# 48-17V_Buck_Converter.net
KiCad netlist of a schematic drawn in Altium Designer
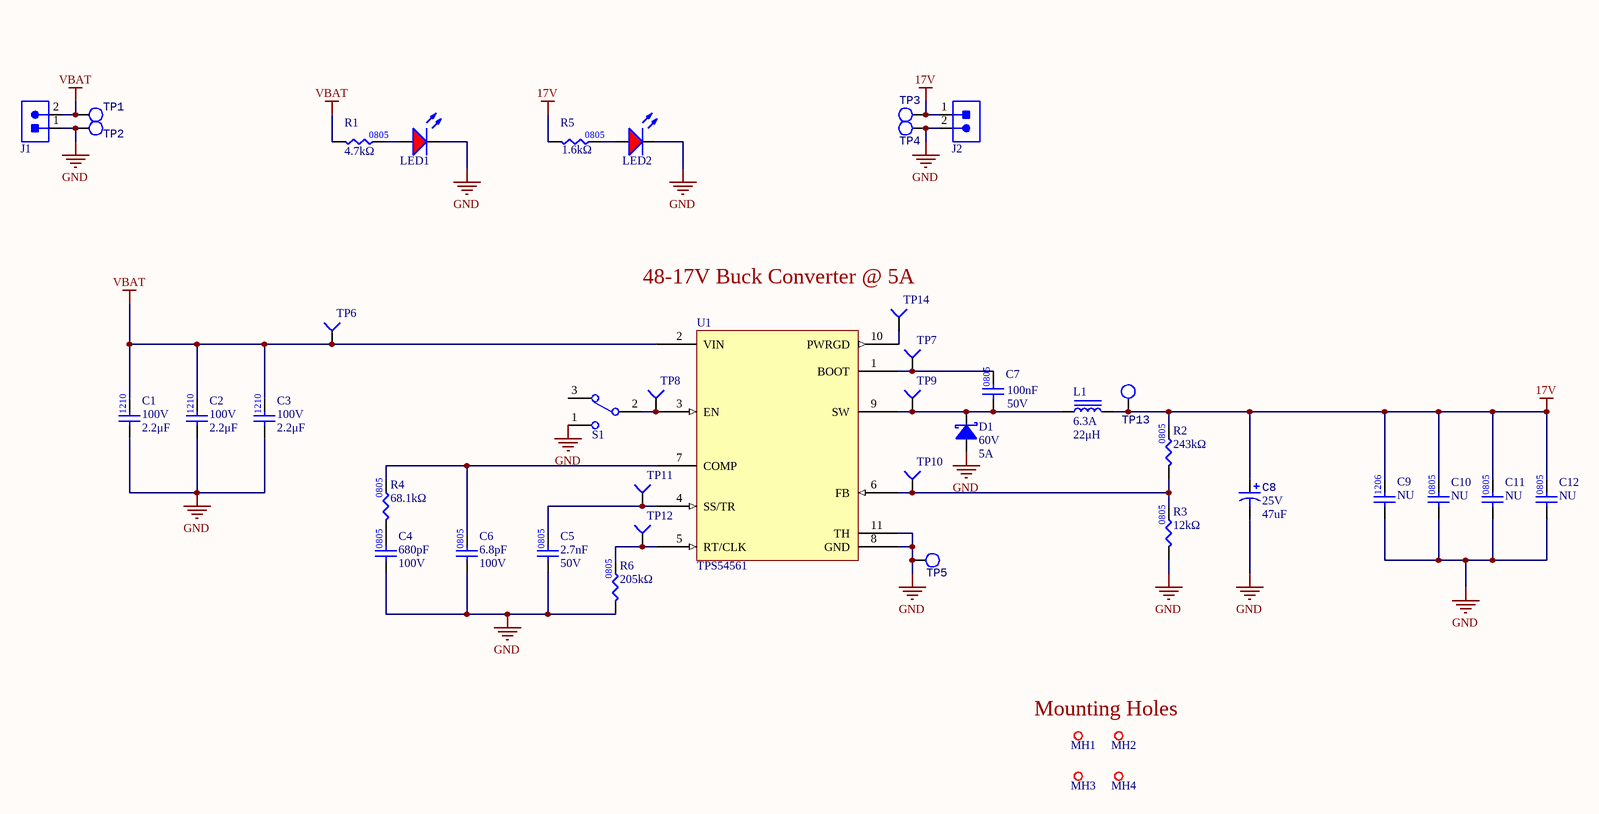
[diagram p0: 48-17V Buck Converter.SchDoc]

(export (version "E")
  (design (tool "Eeschema 10.0.6"))
  (components
    (comp (ref "C1")
      (value "2.2μF")
      (footprint "CAPC3225X270N")
      (description "CAP CER 2.2UF 100V X7R 1210")
      (fields (field (name "VOLTAGE RATING") "100V") (field (name "Comment") "CAP_2.2uF_100V_1210_1"))
      (libsource (lib "UWRT_Schematic_Library_2020") (part "CAP_2.2uF_100V_1210_1"))
    )
    (comp (ref "C2")
      (value "2.2μF")
      (footprint "CAPC3225X270N")
      (description "CAP CER 2.2UF 100V X7R 1210")
      (fields (field (name "VOLTAGE RATING") "100V") (field (name "Comment") "CAP_2.2uF_100V_1210_1"))
      (libsource (lib "UWRT_Schematic_Library_2020") (part "CAP_2.2uF_100V_1210_1"))
    )
    (comp (ref "C3")
      (value "2.2μF")
      (footprint "CAPC3225X270N")
      (description "CAP CER 2.2UF 100V X7R 1210")
      (fields (field (name "VOLTAGE RATING") "100V") (field (name "Comment") "CAP_2.2uF_100V_1210_1"))
      (libsource (lib "UWRT_Schematic_Library_2020") (part "CAP_2.2uF_100V_1210_1"))
    )
    (comp (ref "C4")
      (value "680pF")
      (footprint "CAP0805")
      (description "CAP CER 680PF 100V C0G/NP0 0805")
      (fields (field (name "VOLTAGE RATING") "100V") (field (name "Comment") "CAP_680pF_50V_0805"))
      (libsource (lib "UWRT_Schematic_Library_2020") (part "CAP_680pF_50V_0805"))
    )
    (comp (ref "C5")
      (value "2.7nF")
      (footprint "CAP0805")
      (description "CAP CER 2700PF 50V C0G 0805")
      (fields (field (name "VOLTAGE RATING") "50V") (field (name "Comment") "CAP_2.7nF_50V_0805"))
      (libsource (lib "UWRT_Schematic_Library_2020") (part "CAP_2.7nF_50V_0805"))
    )
    (comp (ref "C6")
      (value "6.8pF")
      (footprint "CAP0805")
      (description "CAP CER 6.8PF 100V C0G/NP0 0805")
      (fields (field (name "VOLTAGE RATING") "100V") (field (name "Comment") "CAP_6.8pF_100V_0805"))
      (libsource (lib "UWRT_Schematic_Library_2020") (part "CAP_6.8pF_100V_0805"))
    )
    (comp (ref "C7")
      (value "100nF")
      (footprint "CAP0805")
      (description "CAP CER 0.1UF 50V X7R 0805")
      (fields (field (name "VOLTAGE RATING") "50V") (field (name "Comment") "CAP_100nF_50V_0805"))
      (libsource (lib "UWRT_Schematic_Library_2020") (part "CAP_100nF_50V_0805"))
    )
    (comp (ref "C8")
      (value "47uF")
      (footprint "CAP_47uF_25V_ALUM")
      (description "CAP ALUM POLY 47UF 20% 25V SMD")
      (fields (field (name "VOLTAGE") "25V") (field (name "Comment") "CAP_47uF_25V_ALUM"))
      (libsource (lib "UWRT_Schematic_Library_2020") (part "CAP_47uF_25V_ALUM"))
    )
    (comp (ref "C9")
      (value "NU")
      (footprint "CAP1206")
      (description "PLACEHOLDER CAPACITOR")
      (fields (field (name "Comment") "CAP_NU_1206"))
      (libsource (lib "UWRT_Schematic_Library_2020") (part "CAP_NU_1206"))
    )
    (comp (ref "C10")
      (value "NU")
      (footprint "CAP0805")
      (description "PLACEHOLDER CAPACITOR")
      (fields (field (name "Comment") "CAP_NU_0805"))
      (libsource (lib "UWRT_Schematic_Library_2020") (part "CAP_NU_0805"))
    )
    (comp (ref "C11")
      (value "NU")
      (footprint "CAP0805")
      (description "PLACEHOLDER CAPACITOR")
      (fields (field (name "Comment") "CAP_NU_0805"))
      (libsource (lib "UWRT_Schematic_Library_2020") (part "CAP_NU_0805"))
    )
    (comp (ref "C12")
      (value "NU")
      (footprint "CAP0805")
      (description "PLACEHOLDER CAPACITOR")
      (fields (field (name "Comment") "CAP_NU_0805"))
      (libsource (lib "UWRT_Schematic_Library_2020") (part "CAP_NU_0805"))
    )
    (comp (ref "D1")
      (value "DIO_SCHOTTKY_30V_800mA")
      (footprint "SOD-323_UNIDIR")
      (description "DIODE SCHOTTKY 60V 5A SMC")
      (fields (field (name "VR (MAX)") "60V") (field (name "IO") "5A"))
      (libsource (lib "UWRT_Schematic_Library_2020") (part "DIO_SCHOTTKY_60V_5A"))
    )
    (comp (ref "J1")
      (value "CON_2POS_SCREW_TERM")
      (footprint "1935161")
      (description "TERM BLK 2POS SIDE ENTRY 5MM")
      (libsource (lib "UWRT_Schematic_Library_2020") (part "CON_2POS_SCREW_TERM"))
    )
    (comp (ref "J2")
      (value "CON_2POS_SCREW_TERM")
      (footprint "1935161")
      (description "TERM BLK 2POS SIDE ENTRY 5MM")
      (libsource (lib "") (part "CON_2POS_SCREW_TERM_1"))
    )
    (comp (ref "L1")
      (value "IND_22uH_6.3A")
      (footprint "UWRT_Footprint_Library_2020:IND_22uH_6.3A")
      (description "FIXED IND 22UH 6.3A 25.7MOHM SMD")
      (fields (field (name "CURRENT RATING") "6.3A") (field (name "INDUCTANCE") "22μH"))
      (libsource (lib "UWRT_Schematic_Library_2020") (part "IND_22uH_6.3A"))
    )
    (comp (ref "LED1")
      (value "LED_RED")
      (footprint "LED_0805_RED")
      (description "LED RED DIFFUSED 0805 SMD")
      (libsource (lib "UWRT_Schematic_Library_2020") (part "LED_RED"))
    )
    (comp (ref "LED2")
      (value "LED_RED")
      (footprint "LED_0805_RED")
      (description "LED RED DIFFUSED 0805 SMD")
      (libsource (lib "UWRT_Schematic_Library_2020") (part "LED_RED"))
    )
    (comp (ref "MH1")
      (value "MOUNTING_HOLE_M3_GIMBAL_REV2")
      (footprint "MOUNTING_HOLE_3mm_GIMBAL_REV2")
      (description "MOUNTING_HOLE_M3 Gimbal Rev2")
      (libsource (lib "UWRT_Schematic_Library_2020") (part "MOUNTING_HOLE_M3_GIMBAL_REV2"))
    )
    (comp (ref "MH2")
      (value "MOUNTING_HOLE_M3_GIMBAL_REV2")
      (footprint "MOUNTING_HOLE_3mm_GIMBAL_REV2")
      (description "MOUNTING_HOLE_M3 Gimbal Rev2")
      (libsource (lib "UWRT_Schematic_Library_2020") (part "MOUNTING_HOLE_M3_GIMBAL_REV2"))
    )
    (comp (ref "MH3")
      (value "MOUNTING_HOLE_M3_GIMBAL_REV2")
      (footprint "MOUNTING_HOLE_3mm_GIMBAL_REV2")
      (description "MOUNTING_HOLE_M3 Gimbal Rev2")
      (libsource (lib "UWRT_Schematic_Library_2020") (part "MOUNTING_HOLE_M3_GIMBAL_REV2"))
    )
    (comp (ref "MH4")
      (value "MOUNTING_HOLE_M3_GIMBAL_REV2")
      (footprint "MOUNTING_HOLE_3mm_GIMBAL_REV2")
      (description "MOUNTING_HOLE_M3 Gimbal Rev2")
      (libsource (lib "UWRT_Schematic_Library_2020") (part "MOUNTING_HOLE_M3_GIMBAL_REV2"))
    )
    (comp (ref "R1")
      (value "4.7kΩ")
      (footprint "RES0805")
      (description "RES 4.7K OHM 5% 1/8W 0805")
      (fields (field (name "LCSC PART #") "C17673") (field (name "Comment") "RES_4.7kΩ_0805_5%"))
      (libsource (lib "UWRT_Schematic_Library_2020") (part "RES_4.7kΩ_0805_5%"))
    )
    (comp (ref "R2")
      (value "243kΩ")
      (footprint "RES0805")
      (description "RES 243K OHM 1% 1/8W 0805")
      (fields (field (name "Comment") "RES_243kΩ_0805_1%_1"))
      (libsource (lib "UWRT_Schematic_Library_2020") (part "RES_243kΩ_0805_1%_1"))
    )
    (comp (ref "R3")
      (value "12kΩ")
      (footprint "RES0805")
      (description "RES 12K OHM 1% 1/8W 0805")
      (fields (field (name "Comment") "RES_12kΩ_0805_1%"))
      (libsource (lib "UWRT_Schematic_Library_2020") (part "RES_12kΩ_0805_1%"))
    )
    (comp (ref "R4")
      (value "68.1kΩ")
      (footprint "RES0805")
      (description "RES 68.1K OHM 1% 1/8W 0805")
      (fields (field (name "Comment") "RES_68.1kΩ_0805_1%"))
      (libsource (lib "UWRT_Schematic_Library_2020") (part "RES_68.1kΩ_0805_1%"))
    )
    (comp (ref "R5")
      (value "1.6kΩ")
      (footprint "RES0805")
      (description "RES 1.6K OHM 0.1% 1/4W 0805")
      (fields (field (name "TOLERANCE") "0.1%") (field (name "Comment") "RES_1.6kΩ_0805_0.1%"))
      (libsource (lib "UWRT_Schematic_Library_2020") (part "RES_1.6kΩ_0805_0.1%"))
    )
    (comp (ref "R6")
      (value "205kΩ")
      (footprint "RES0805")
      (description "RES 205K OHM 1% 1/8W 0805")
      (fields (field (name "Comment") "RES_205kΩ_0805_1%"))
      (libsource (lib "UWRT_Schematic_Library_2020") (part "RES_205kΩ_0805_1%"))
    )
    (comp (ref "S1")
      (value "SW_SLIDE_TOGGLE")
      (footprint "UWRT_Footprint_Library_2020:SW_SLIDE_TOGGLE")
      (description "SWITCH SLIDE SPDT 200MA 30V")
      (libsource (lib "UWRT_Schematic_Library_2020") (part "SW_SLIDE_TOGGLE"))
    )
    (comp (ref "TP1")
      (value "TESTPOINT_LOOP")
      (footprint "TESTPOINT_LOOP")
      (description "TESTPOINT THRUHOLE")
      (libsource (lib "UWRT_Schematic_Library_2020") (part "TESTPOINT_LOOP"))
    )
    (comp (ref "TP2")
      (value "TESTPOINT_LOOP")
      (footprint "TESTPOINT_LOOP")
      (description "TESTPOINT THRUHOLE")
      (libsource (lib "UWRT_Schematic_Library_2020") (part "TESTPOINT_LOOP"))
    )
    (comp (ref "TP3")
      (value "TESTPOINT_LOOP")
      (footprint "TESTPOINT_LOOP")
      (description "TESTPOINT THRUHOLE")
      (libsource (lib "UWRT_Schematic_Library_2020") (part "TESTPOINT_LOOP"))
    )
    (comp (ref "TP4")
      (value "TESTPOINT_LOOP")
      (footprint "TESTPOINT_LOOP")
      (description "TESTPOINT THRUHOLE")
      (libsource (lib "UWRT_Schematic_Library_2020") (part "TESTPOINT_LOOP"))
    )
    (comp (ref "TP5")
      (value "TESTPOINT_LOOP")
      (footprint "TESTPOINT_LOOP")
      (description "TESTPOINT THRUHOLE")
      (libsource (lib "UWRT_Schematic_Library_2020") (part "TESTPOINT_LOOP"))
    )
    (comp (ref "TP6")
      (value "TESTPOINT_1MM_CIRCLE")
      (footprint "TESTPOINT_CIRCLE_1MM")
      (description "TESTPOINT 1MM CIRCLE")
      (libsource (lib "UWRT_Schematic_Library_2020") (part "TESTPOINT_1MM_CIRCLE"))
    )
    (comp (ref "TP7")
      (value "TESTPOINT_1MM_CIRCLE")
      (footprint "TESTPOINT_CIRCLE_1MM")
      (description "TESTPOINT 1MM CIRCLE")
      (libsource (lib "UWRT_Schematic_Library_2020") (part "TESTPOINT_1MM_CIRCLE"))
    )
    (comp (ref "TP8")
      (value "TESTPOINT_1MM_CIRCLE")
      (footprint "TESTPOINT_CIRCLE_1MM")
      (description "TESTPOINT 1MM CIRCLE")
      (libsource (lib "UWRT_Schematic_Library_2020") (part "TESTPOINT_1MM_CIRCLE"))
    )
    (comp (ref "TP9")
      (value "TESTPOINT_1MM_CIRCLE")
      (footprint "TESTPOINT_CIRCLE_1MM")
      (description "TESTPOINT 1MM CIRCLE")
      (libsource (lib "UWRT_Schematic_Library_2020") (part "TESTPOINT_1MM_CIRCLE"))
    )
    (comp (ref "TP10")
      (value "TESTPOINT_1MM_CIRCLE")
      (footprint "TESTPOINT_CIRCLE_1MM")
      (description "TESTPOINT 1MM CIRCLE")
      (libsource (lib "UWRT_Schematic_Library_2020") (part "TESTPOINT_1MM_CIRCLE"))
    )
    (comp (ref "TP11")
      (value "TESTPOINT_1MM_CIRCLE")
      (footprint "TESTPOINT_CIRCLE_1MM")
      (description "TESTPOINT 1MM CIRCLE")
      (libsource (lib "UWRT_Schematic_Library_2020") (part "TESTPOINT_1MM_CIRCLE"))
    )
    (comp (ref "TP12")
      (value "TESTPOINT_1MM_CIRCLE")
      (footprint "TESTPOINT_CIRCLE_1MM")
      (description "TESTPOINT 1MM CIRCLE")
      (libsource (lib "UWRT_Schematic_Library_2020") (part "TESTPOINT_1MM_CIRCLE"))
    )
    (comp (ref "TP13")
      (value "TESTPOINT_LOOP")
      (footprint "TESTPOINT_LOOP")
      (description "TESTPOINT THRUHOLE")
      (libsource (lib "UWRT_Schematic_Library_2020") (part "TESTPOINT_LOOP"))
    )
    (comp (ref "TP14")
      (value "TESTPOINT_1MM_CIRCLE")
      (footprint "TESTPOINT_CIRCLE_1MM")
      (description "TESTPOINT 1MM CIRCLE")
      (libsource (lib "UWRT_Schematic_Library_2020") (part "TESTPOINT_1MM_CIRCLE"))
    )
    (comp (ref "U1")
      (value "TPS54561")
      (footprint "BUCK_TPS54561DPRR")
      (description "Buck Switching Regulator IC Positive Adjustable 0.8V 1 Output 5A 10-WDFN Exposed Pad")
      (libsource (lib "UWRT_Schematic_Library_2020") (part "TPS54561"))
    )
  )
  (nets
    (net (code "1") (name "17V") (class "Default")
      (node (ref "C10") (pin "2") (pinfunction "2_2") (pintype "passive"))
      (node (ref "C11") (pin "2") (pinfunction "2_2") (pintype "passive"))
      (node (ref "C12") (pin "2") (pinfunction "2_2") (pintype "passive"))
      (node (ref "C8") (pin "1") (pinfunction "1_1") (pintype "passive"))
      (node (ref "C9") (pin "2") (pinfunction "2_2") (pintype "passive"))
      (node (ref "J2") (pin "1") (pinfunction "1_1") (pintype "passive"))
      (node (ref "L1") (pin "2") (pinfunction "2_2") (pintype "passive"))
      (node (ref "R2") (pin "2") (pinfunction "2_2") (pintype "passive"))
      (node (ref "R5") (pin "1") (pinfunction "1_1") (pintype "passive"))
      (node (ref "TP13") (pin "1") (pintype "passive"))
      (node (ref "TP3") (pin "1") (pintype "passive"))
    )
    (net (code "2") (name "GND") (class "Default")
      (node (ref "C1") (pin "1") (pinfunction "1_1") (pintype "passive"))
      (node (ref "C10") (pin "1") (pinfunction "1_1") (pintype "passive"))
      (node (ref "C11") (pin "1") (pinfunction "1_1") (pintype "passive"))
      (node (ref "C12") (pin "1") (pinfunction "1_1") (pintype "passive"))
      (node (ref "C2") (pin "1") (pinfunction "1_1") (pintype "passive"))
      (node (ref "C3") (pin "1") (pinfunction "1_1") (pintype "passive"))
      (node (ref "C4") (pin "1") (pinfunction "1_1") (pintype "passive"))
      (node (ref "C5") (pin "1") (pinfunction "1_1") (pintype "passive"))
      (node (ref "C6") (pin "1") (pinfunction "1_1") (pintype "passive"))
      (node (ref "C8") (pin "2") (pinfunction "2_2") (pintype "passive"))
      (node (ref "C9") (pin "1") (pinfunction "1_1") (pintype "passive"))
      (node (ref "D1") (pin "1") (pinfunction "Anode_1") (pintype "passive"))
      (node (ref "J1") (pin "1") (pinfunction "1_1") (pintype "passive"))
      (node (ref "J2") (pin "2") (pinfunction "2_2") (pintype "passive"))
      (node (ref "LED1") (pin "2") (pinfunction "K_2") (pintype "passive"))
      (node (ref "LED2") (pin "2") (pinfunction "K_2") (pintype "passive"))
      (node (ref "R3") (pin "1") (pinfunction "1_1") (pintype "passive"))
      (node (ref "R6") (pin "1") (pinfunction "1_1") (pintype "passive"))
      (node (ref "S1") (pin "1") (pinfunction "1_1") (pintype "passive"))
      (node (ref "TP2") (pin "1") (pintype "passive"))
      (node (ref "TP4") (pin "1") (pintype "passive"))
      (node (ref "TP5") (pin "1") (pintype "passive"))
      (node (ref "U1") (pin "11") (pinfunction "TH_11") (pintype "power_in"))
      (node (ref "U1") (pin "8") (pinfunction "GND_8") (pintype "power_in"))
    )
    (net (code "3") (name "Net-(C4-Pad2)") (class "Default")
      (node (ref "C4") (pin "2") (pinfunction "2_2") (pintype "passive"))
      (node (ref "R4") (pin "1") (pinfunction "1_1") (pintype "passive"))
    )
    (net (code "4") (name "Net-(D1-Cathode)") (class "Default")
      (node (ref "C7") (pin "1") (pinfunction "1_1") (pintype "passive"))
      (node (ref "D1") (pin "2") (pinfunction "Cathode_2") (pintype "passive"))
      (node (ref "L1") (pin "1") (pinfunction "1_1") (pintype "passive"))
      (node (ref "TP9") (pin "1") (pinfunction "=value_1") (pintype "passive"))
      (node (ref "U1") (pin "9") (pinfunction "SW_9") (pintype "power_in"))
    )
    (net (code "5") (name "Net-(LED1-A)") (class "Default")
      (node (ref "LED1") (pin "1") (pinfunction "A_1") (pintype "passive"))
      (node (ref "R1") (pin "2") (pinfunction "2_2") (pintype "passive"))
    )
    (net (code "6") (name "Net-(LED2-A)") (class "Default")
      (node (ref "LED2") (pin "1") (pinfunction "A_1") (pintype "passive"))
      (node (ref "R5") (pin "2") (pinfunction "2_2") (pintype "passive"))
    )
    (net (code "7") (name "Net-(TP7-=value)") (class "Default")
      (node (ref "C7") (pin "2") (pinfunction "2_2") (pintype "passive"))
      (node (ref "TP7") (pin "1") (pinfunction "=value_1") (pintype "passive"))
      (node (ref "U1") (pin "1") (pinfunction "BOOT_1") (pintype "power_in"))
    )
    (net (code "8") (name "Net-(TP8-=value)") (class "Default")
      (node (ref "S1") (pin "2") (pinfunction "2_2") (pintype "passive"))
      (node (ref "TP8") (pin "1") (pinfunction "=value_1") (pintype "passive"))
      (node (ref "U1") (pin "3") (pinfunction "EN_3") (pintype "input"))
    )
    (net (code "9") (name "Net-(TP10-=value)") (class "Default")
      (node (ref "R2") (pin "1") (pinfunction "1_1") (pintype "passive"))
      (node (ref "R3") (pin "2") (pinfunction "2_2") (pintype "passive"))
      (node (ref "TP10") (pin "1") (pinfunction "=value_1") (pintype "passive"))
      (node (ref "U1") (pin "6") (pinfunction "FB_6") (pintype "input"))
    )
    (net (code "10") (name "Net-(TP11-=value)") (class "Default")
      (node (ref "C5") (pin "2") (pinfunction "2_2") (pintype "passive"))
      (node (ref "TP11") (pin "1") (pinfunction "=value_1") (pintype "passive"))
      (node (ref "U1") (pin "4") (pinfunction "SS/TR_4") (pintype "input"))
    )
    (net (code "11") (name "Net-(TP12-=value)") (class "Default")
      (node (ref "R6") (pin "2") (pinfunction "2_2") (pintype "passive"))
      (node (ref "TP12") (pin "1") (pinfunction "=value_1") (pintype "passive"))
      (node (ref "U1") (pin "5") (pinfunction "RT/CLK_5") (pintype "input"))
    )
    (net (code "12") (name "Net-(TP14-=value)") (class "Default")
      (node (ref "TP14") (pin "1") (pinfunction "=value_1") (pintype "passive"))
      (node (ref "U1") (pin "10") (pinfunction "PWRGD_10") (pintype "output"))
    )
    (net (code "13") (name "Net-(U1-COMP)") (class "Default")
      (node (ref "C6") (pin "2") (pinfunction "2_2") (pintype "passive"))
      (node (ref "R4") (pin "2") (pinfunction "2_2") (pintype "passive"))
      (node (ref "U1") (pin "7") (pinfunction "COMP_7") (pintype "power_in"))
    )
    (net (code "14") (name "VBAT") (class "Default")
      (node (ref "C1") (pin "2") (pinfunction "2_2") (pintype "passive"))
      (node (ref "C2") (pin "2") (pinfunction "2_2") (pintype "passive"))
      (node (ref "C3") (pin "2") (pinfunction "2_2") (pintype "passive"))
      (node (ref "J1") (pin "2") (pinfunction "2_2") (pintype "passive"))
      (node (ref "R1") (pin "1") (pinfunction "1_1") (pintype "passive"))
      (node (ref "TP1") (pin "1") (pintype "passive"))
      (node (ref "TP6") (pin "1") (pinfunction "=value_1") (pintype "passive"))
      (node (ref "U1") (pin "2") (pinfunction "VIN_2") (pintype "power_in"))
    )
    (net (code "15") (name "unconnected-(S1-Pad3)") (class "Default")
      (node (ref "S1") (pin "3") (pinfunction "3_3") (pintype "passive"))
    )
  )
)
